# FunctionalSchematic.net
KiCad netlist of a schematic drawn in Altium Designer
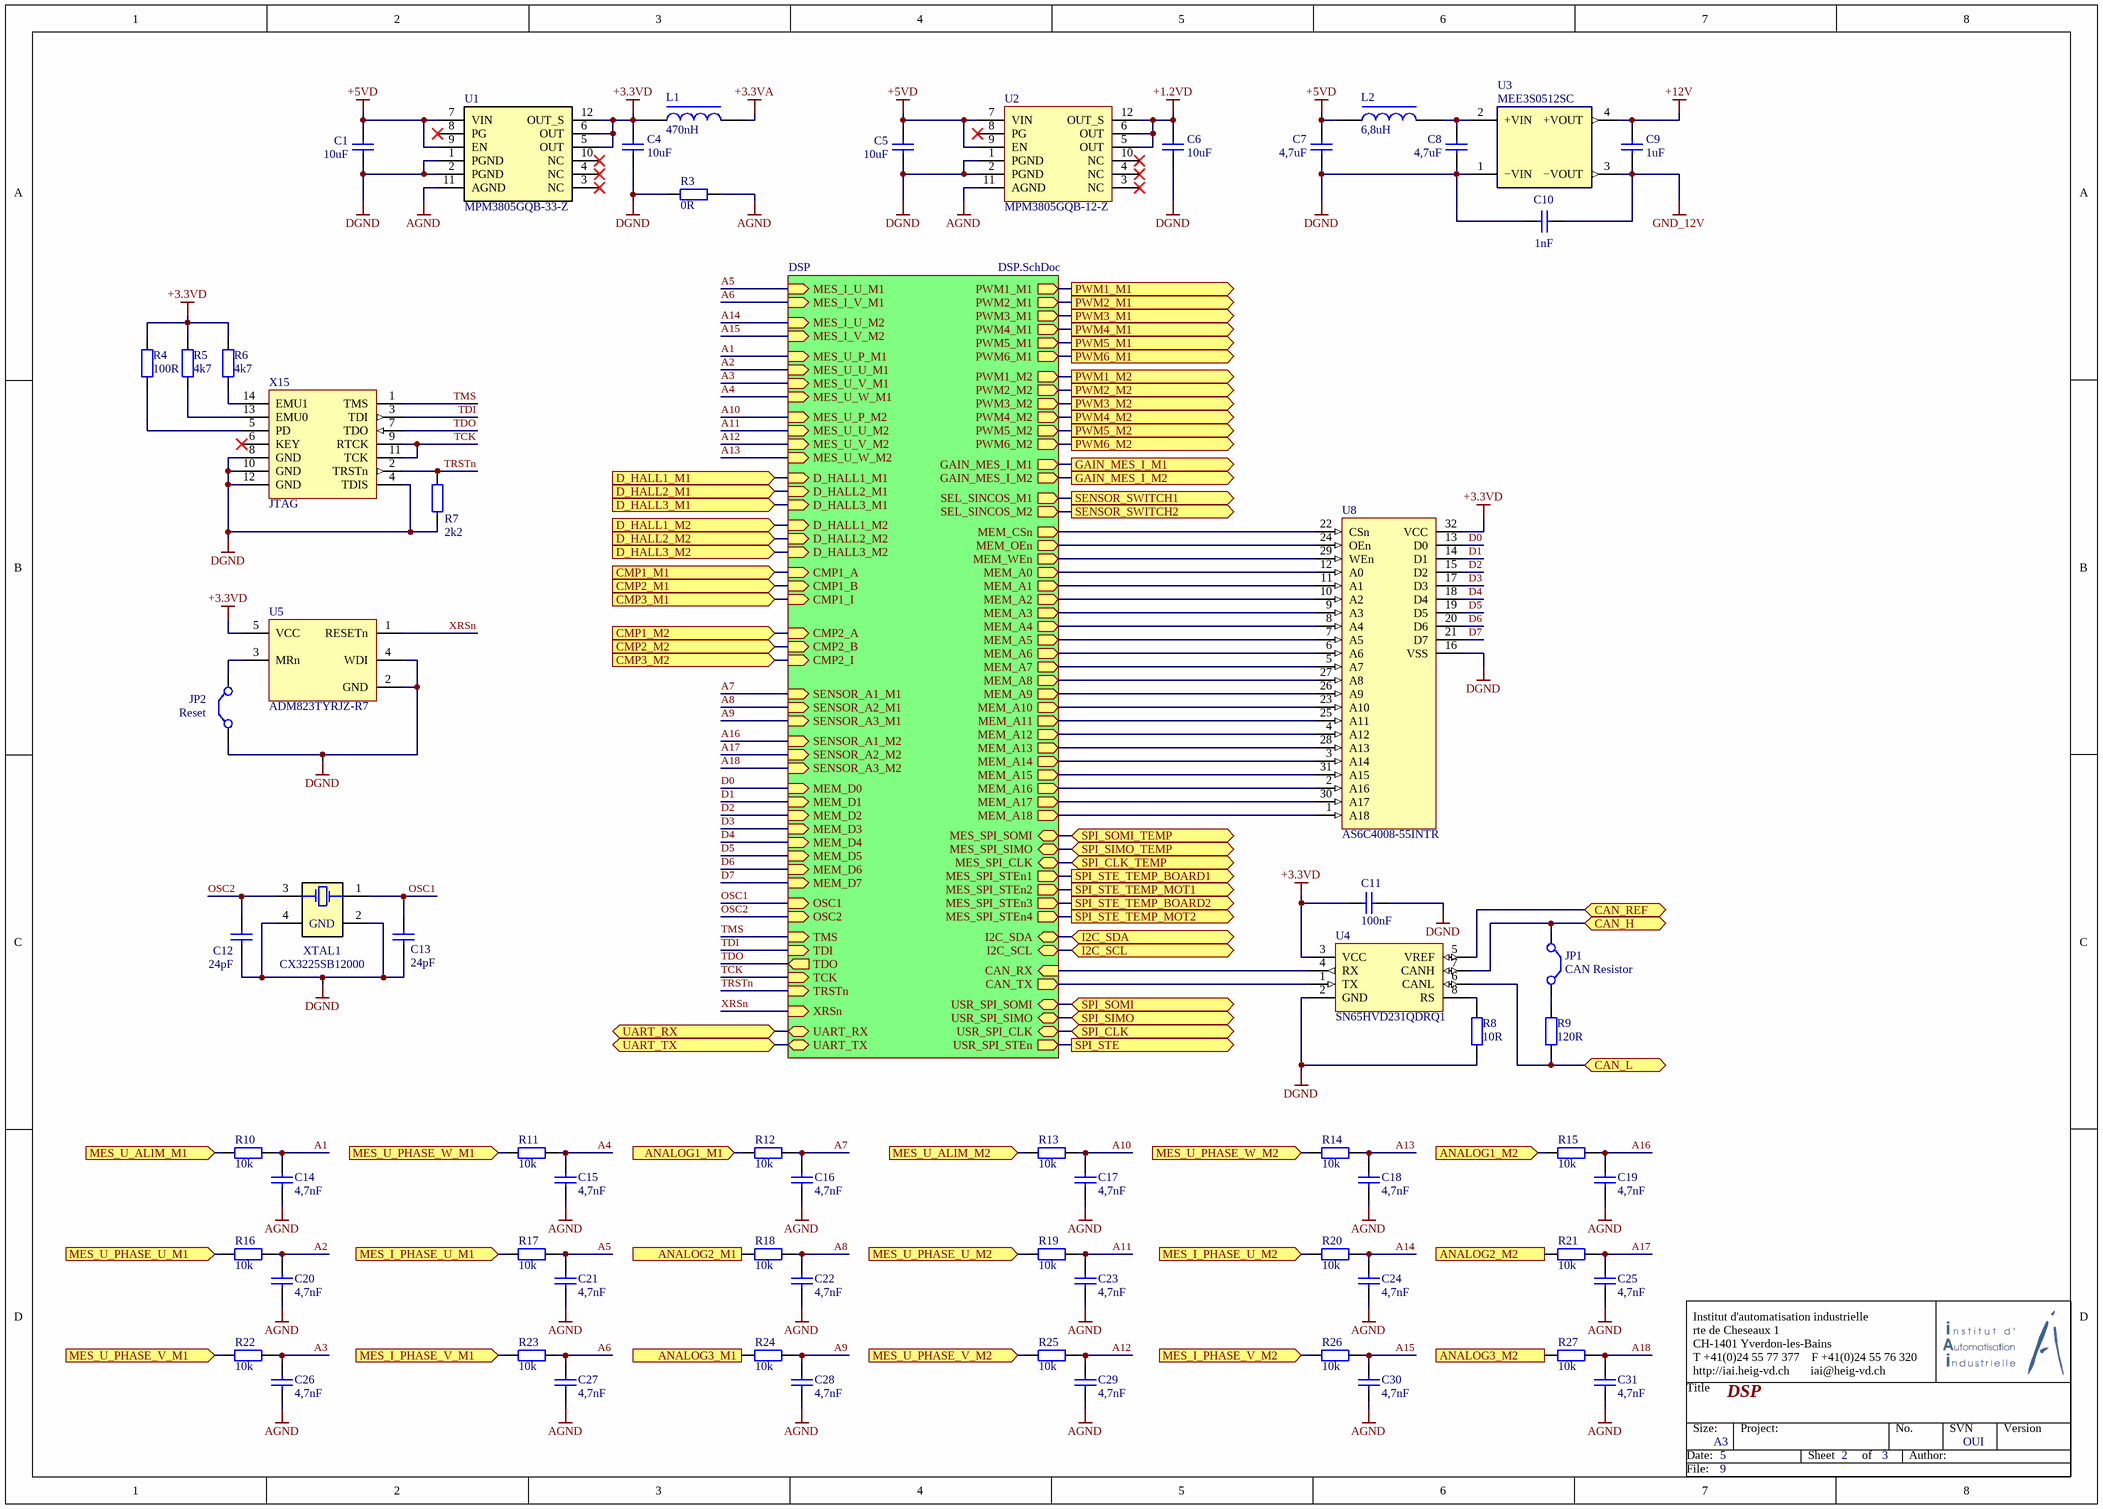
[diagram p0: FunctionalSchematic.SchDoc]

(export (version "E")
  (design (tool "Eeschema 10.0.6"))
  (components
    (comp (ref "C1")
      (value "10uF")
      (footprint "CommandBoard:CAPC1608X08N")
      (description "10µF ±20% 10V Condensateurs céramique X5R 0603 (1608 métrique)")
      (fields (field (name "Comment") "CAP CER 10uF 0603"))
      (libsource (lib "CommandBoard") (part "CAP CER 10uF 10% 10V 0603"))
    )
    (comp (ref "C4")
      (value "10uF")
      (footprint "CommandBoard:CAPC1608X08N")
      (description "10µF ±20% 10V Condensateurs céramique X5R 0603 (1608 métrique)")
      (fields (field (name "Comment") "CAP CER 10uF 0603"))
      (libsource (lib "CommandBoard") (part "CAP CER 10uF 10% 10V 0603"))
    )
    (comp (ref "C5")
      (value "10uF")
      (footprint "CommandBoard:CAPC1608X08N")
      (description "10µF ±20% 10V Condensateurs céramique X5R 0603 (1608 métrique)")
      (fields (field (name "Comment") "CAP CER 10uF 0603"))
      (libsource (lib "CommandBoard") (part "CAP CER 10uF 10% 10V 0603"))
    )
    (comp (ref "C6")
      (value "10uF")
      (footprint "CommandBoard:CAPC1608X08N")
      (description "10µF ±20% 10V Condensateurs céramique X5R 0603 (1608 métrique)")
      (fields (field (name "Comment") "CAP CER 10uF 0603"))
      (libsource (lib "CommandBoard") (part "CAP CER 10uF 10% 10V 0603"))
    )
    (comp (ref "C7")
      (value "4,7uF")
      (footprint "CommandBoard:CAPC1608X08N")
      (description "4,7µF ±20% 10V Condensateurs céramique X5R 0603 (1608 métrique)")
      (fields (field (name "Comment") "CAP CER 4.7uF 0603"))
      (libsource (lib "CommandBoard") (part "CAP CER 4.7uF 10% 10V 0603"))
    )
    (comp (ref "C8")
      (value "4,7uF")
      (footprint "CommandBoard:CAPC1608X08N")
      (description "4,7µF ±20% 10V Condensateurs céramique X5R 0603 (1608 métrique)")
      (fields (field (name "Comment") "CAP CER 4.7uF 0603"))
      (libsource (lib "CommandBoard") (part "CAP CER 4.7uF 10% 10V 0603"))
    )
    (comp (ref "C9")
      (value "1uF")
      (footprint "CommandBoard:CAPC1608X08N")
      (description "1µF ±10% 16V Condensateurs céramique X7R 0603 (1608 métrique)")
      (fields (field (name "Comment") "CAP CER 1uF 0603"))
      (libsource (lib "CommandBoard") (part "CAP CER 1uF 10% 16V 0603"))
    )
    (comp (ref "C10")
      (value "1nF")
      (footprint "CommandBoard:CAPC1608X08N")
      (description "1nF ±10% 10V Condensateurs céramique X7R 0603 (1608 métrique)")
      (fields (field (name "Comment") "CAP CER 1nF 0603"))
      (libsource (lib "CommandBoard") (part "CAP CER 1nF 10% 10V 0603"))
    )
    (comp (ref "C11")
      (value "100nF")
      (footprint "CommandBoard:CAPC1608X08N")
      (description "0,1µF ±10% 10V Condensateurs céramique X7R 0603 (1608 métrique)")
      (fields (field (name "Comment") "CAP CER 100nF 0603"))
      (libsource (lib "CommandBoard") (part "CAP CER 100nF 10% 10V 0603"))
    )
    (comp (ref "C12")
      (value "24pF")
      (footprint "CommandBoard:CAPC1608X08N")
      (description "24pF ±10% 10V Condensateurs céramique X7R 0603 (1608 métrique)")
      (fields (field (name "Comment") "CAP CER 1nF 0603"))
      (libsource (lib "CommandBoard") (part "CAP CER 24pF 10% 10V 0603"))
    )
    (comp (ref "C13")
      (value "24pF")
      (footprint "CommandBoard:CAPC1608X08N")
      (description "24pF ±10% 10V Condensateurs céramique X7R 0603 (1608 métrique)")
      (fields (field (name "Comment") "CAP CER 1nF 0603"))
      (libsource (lib "CommandBoard") (part "CAP CER 24pF 10% 10V 0603"))
    )
    (comp (ref "C14")
      (value "4,7nF")
      (footprint "CommandBoard:CAPC1608X08N")
      (description "4,7nF ±10% 10V Condensateurs céramique X7R 0603 (1608 métrique)")
      (fields (field (name "Comment") "CAP CER 4.7nF 0603"))
      (libsource (lib "CommandBoard") (part "CAP CER 4.7nF 10% 10V 0603"))
    )
    (comp (ref "C15")
      (value "4,7nF")
      (footprint "CommandBoard:CAPC1608X08N")
      (description "4,7nF ±10% 10V Condensateurs céramique X7R 0603 (1608 métrique)")
      (fields (field (name "Comment") "CAP CER 4.7nF 0603"))
      (libsource (lib "CommandBoard") (part "CAP CER 4.7nF 10% 10V 0603"))
    )
    (comp (ref "C16")
      (value "4,7nF")
      (footprint "CommandBoard:CAPC1608X08N")
      (description "4,7nF ±10% 10V Condensateurs céramique X7R 0603 (1608 métrique)")
      (fields (field (name "Comment") "CAP CER 4.7nF 0603"))
      (libsource (lib "CommandBoard") (part "CAP CER 4.7nF 10% 10V 0603"))
    )
    (comp (ref "C17")
      (value "4,7nF")
      (footprint "CommandBoard:CAPC1608X08N")
      (description "4,7nF ±10% 10V Condensateurs céramique X7R 0603 (1608 métrique)")
      (fields (field (name "Comment") "CAP CER 4.7nF 0603"))
      (libsource (lib "CommandBoard") (part "CAP CER 4.7nF 10% 10V 0603"))
    )
    (comp (ref "C18")
      (value "4,7nF")
      (footprint "CommandBoard:CAPC1608X08N")
      (description "4,7nF ±10% 10V Condensateurs céramique X7R 0603 (1608 métrique)")
      (fields (field (name "Comment") "CAP CER 4.7nF 0603"))
      (libsource (lib "CommandBoard") (part "CAP CER 4.7nF 10% 10V 0603"))
    )
    (comp (ref "C19")
      (value "4,7nF")
      (footprint "CommandBoard:CAPC1608X08N")
      (description "4,7nF ±10% 10V Condensateurs céramique X7R 0603 (1608 métrique)")
      (fields (field (name "Comment") "CAP CER 4.7nF 0603"))
      (libsource (lib "CommandBoard") (part "CAP CER 4.7nF 10% 10V 0603"))
    )
    (comp (ref "C20")
      (value "4,7nF")
      (footprint "CommandBoard:CAPC1608X08N")
      (description "4,7nF ±10% 10V Condensateurs céramique X7R 0603 (1608 métrique)")
      (fields (field (name "Comment") "CAP CER 4.7nF 0603"))
      (libsource (lib "CommandBoard") (part "CAP CER 4.7nF 10% 10V 0603"))
    )
    (comp (ref "C21")
      (value "4,7nF")
      (footprint "CommandBoard:CAPC1608X08N")
      (description "4,7nF ±10% 10V Condensateurs céramique X7R 0603 (1608 métrique)")
      (fields (field (name "Comment") "CAP CER 4.7nF 0603"))
      (libsource (lib "CommandBoard") (part "CAP CER 4.7nF 10% 10V 0603"))
    )
    (comp (ref "C22")
      (value "4,7nF")
      (footprint "CommandBoard:CAPC1608X08N")
      (description "4,7nF ±10% 10V Condensateurs céramique X7R 0603 (1608 métrique)")
      (fields (field (name "Comment") "CAP CER 4.7nF 0603"))
      (libsource (lib "CommandBoard") (part "CAP CER 4.7nF 10% 10V 0603"))
    )
    (comp (ref "C23")
      (value "4,7nF")
      (footprint "CommandBoard:CAPC1608X08N")
      (description "4,7nF ±10% 10V Condensateurs céramique X7R 0603 (1608 métrique)")
      (fields (field (name "Comment") "CAP CER 4.7nF 0603"))
      (libsource (lib "CommandBoard") (part "CAP CER 4.7nF 10% 10V 0603"))
    )
    (comp (ref "C24")
      (value "4,7nF")
      (footprint "CommandBoard:CAPC1608X08N")
      (description "4,7nF ±10% 10V Condensateurs céramique X7R 0603 (1608 métrique)")
      (fields (field (name "Comment") "CAP CER 4.7nF 0603"))
      (libsource (lib "CommandBoard") (part "CAP CER 4.7nF 10% 10V 0603"))
    )
    (comp (ref "C25")
      (value "4,7nF")
      (footprint "CommandBoard:CAPC1608X08N")
      (description "4,7nF ±10% 10V Condensateurs céramique X7R 0603 (1608 métrique)")
      (fields (field (name "Comment") "CAP CER 4.7nF 0603"))
      (libsource (lib "CommandBoard") (part "CAP CER 4.7nF 10% 10V 0603"))
    )
    (comp (ref "C26")
      (value "4,7nF")
      (footprint "CommandBoard:CAPC1608X08N")
      (description "4,7nF ±10% 10V Condensateurs céramique X7R 0603 (1608 métrique)")
      (fields (field (name "Comment") "CAP CER 4.7nF 0603"))
      (libsource (lib "CommandBoard") (part "CAP CER 4.7nF 10% 10V 0603"))
    )
    (comp (ref "C27")
      (value "4,7nF")
      (footprint "CommandBoard:CAPC1608X08N")
      (description "4,7nF ±10% 10V Condensateurs céramique X7R 0603 (1608 métrique)")
      (fields (field (name "Comment") "CAP CER 4.7nF 0603"))
      (libsource (lib "CommandBoard") (part "CAP CER 4.7nF 10% 10V 0603"))
    )
    (comp (ref "C28")
      (value "4,7nF")
      (footprint "CommandBoard:CAPC1608X08N")
      (description "4,7nF ±10% 10V Condensateurs céramique X7R 0603 (1608 métrique)")
      (fields (field (name "Comment") "CAP CER 4.7nF 0603"))
      (libsource (lib "CommandBoard") (part "CAP CER 4.7nF 10% 10V 0603"))
    )
    (comp (ref "C29")
      (value "4,7nF")
      (footprint "CommandBoard:CAPC1608X08N")
      (description "4,7nF ±10% 10V Condensateurs céramique X7R 0603 (1608 métrique)")
      (fields (field (name "Comment") "CAP CER 4.7nF 0603"))
      (libsource (lib "CommandBoard") (part "CAP CER 4.7nF 10% 10V 0603"))
    )
    (comp (ref "C30")
      (value "4,7nF")
      (footprint "CommandBoard:CAPC1608X08N")
      (description "4,7nF ±10% 10V Condensateurs céramique X7R 0603 (1608 métrique)")
      (fields (field (name "Comment") "CAP CER 4.7nF 0603"))
      (libsource (lib "CommandBoard") (part "CAP CER 4.7nF 10% 10V 0603"))
    )
    (comp (ref "C31")
      (value "4,7nF")
      (footprint "CommandBoard:CAPC1608X08N")
      (description "4,7nF ±10% 10V Condensateurs céramique X7R 0603 (1608 métrique)")
      (fields (field (name "Comment") "CAP CER 4.7nF 0603"))
      (libsource (lib "CommandBoard") (part "CAP CER 4.7nF 10% 10V 0603"))
    )
    (comp (ref "JP1")
      (value "CONNECT 2pos 90°")
      (footprint "CommandBoard:62000211121")
      (fields (field (name "USE") "CAN Resistor"))
      (libsource (lib "CommandBoard") (part "CONNECT 2pos 90° 3.81mm"))
    )
    (comp (ref "JP2")
      (value "CONNECT 2pos 90°")
      (footprint "CommandBoard:62000211121")
      (fields (field (name "USE") "Reset"))
      (libsource (lib "CommandBoard") (part "CONNECT 2pos 90° 3.81mm"))
    )
    (comp (ref "L1")
      (value "470nH")
      (footprint "CommandBoard:INDC2016X10N")
      (fields (field (name "Comment") "IND SMD 470nH 0806"))
      (libsource (lib "CommandBoard") (part "IND SMD 470nH 0806"))
    )
    (comp (ref "L2")
      (value "6,8uH")
      (footprint "CommandBoard:INDC1608X10N")
      (description "6,8µH Blindé Multicouche Inducteur 15mA 1,3Ohms maxi 0603 (1608 métrique)")
      (fields (field (name "Comment") "IND SMD 0603"))
      (libsource (lib "CommandBoard") (part "IND SMD 6.8uH 0603"))
    )
    (comp (ref "R3")
      (value "0R")
      (footprint "CommandBoard:RESC1508X04N")
      (description "Resistance 0 OHM")
      (fields (field (name "Comment") "RES SMD 0R 0603"))
      (libsource (lib "CommandBoard") (part "RES SMD 0 OHM 1% 1/10W 0603"))
    )
    (comp (ref "R4")
      (value "100R")
      (footprint "CommandBoard:RESC1508X04N")
      (description "100 Ohms ±1% 0,1W, 1/10W Pavé résistif 0603 (1608 métrique) AutomobileAEC-Q200 Couche épaisse")
      (fields (field (name "Comment") "RES SMD 100R 0603"))
      (libsource (lib "CommandBoard") (part "RES SMD 100 OHM 1% 1/10W 0603"))
    )
    (comp (ref "R5")
      (value "4k7")
      (footprint "CommandBoard:RESC1508X04N")
      (description "4,7 kOhms ±1% 0,1W, 1/10W Pavé résistif 0603 (1608 métrique) AutomobileAEC-Q200 Couche épaisse")
      (fields (field (name "Comment") "RES SMD 4.7k 0603"))
      (libsource (lib "CommandBoard") (part "RES SMD 4.7k OHM 1% 1/10W 0603"))
    )
    (comp (ref "R6")
      (value "4k7")
      (footprint "CommandBoard:RESC1508X04N")
      (description "4,7 kOhms ±1% 0,1W, 1/10W Pavé résistif 0603 (1608 métrique) AutomobileAEC-Q200 Couche épaisse")
      (fields (field (name "Comment") "RES SMD 4.7k 0603"))
      (libsource (lib "CommandBoard") (part "RES SMD 4.7k OHM 1% 1/10W 0603"))
    )
    (comp (ref "R7")
      (value "2k2")
      (footprint "CommandBoard:RESC1508X04N")
      (description "2,2 kOhms ±1% 0,1W, 1/10W Pavé résistif 0603 (1608 métrique) AutomobileAEC-Q200 Couche épaisse")
      (fields (field (name "Comment") "RES SMD 2K2 0603"))
      (libsource (lib "CommandBoard") (part "RES SMD 2K2 OHM 1% 1/10W 0603"))
    )
    (comp (ref "R8")
      (value "10R")
      (footprint "CommandBoard:RESC1508X04N")
      (description "10 Ohms ±1% 0,1W, 1/10W Pavé résistif 0603 (1608 métrique) AutomobileAEC-Q200 Couche épaisse")
      (fields (field (name "Comment") "RES SMD 10R 0603"))
      (libsource (lib "CommandBoard") (part "RES SMD 10 OHM 1% 1/10W 0603"))
    )
    (comp (ref "R9")
      (value "120R")
      (footprint "CommandBoard:RESC1508X04N")
      (description "120 Ohms ±1% 0,1W, 1/10W Pavé résistif 0603 (1608 métrique) AutomobileAEC-Q200 Couche épaisse")
      (fields (field (name "Comment") "RES SMD 120R 0603"))
      (libsource (lib "CommandBoard") (part "RES SMD 120 OHM 1% 1/10W 0603"))
    )
    (comp (ref "R10")
      (value "10k")
      (footprint "CommandBoard:RESC1508X04N")
      (description "10 kOhms ±1% 0,1W, 1/10W Pavé résistif 0603 (1608 métrique) AutomobileAEC-Q200 Couche épaisse")
      (fields (field (name "Comment") "RES 10K SMD 0603"))
      (libsource (lib "CommandBoard") (part "RES SMD 10K OHM 1% 1/10W 0603"))
    )
    (comp (ref "R11")
      (value "10k")
      (footprint "CommandBoard:RESC1508X04N")
      (description "10 kOhms ±1% 0,1W, 1/10W Pavé résistif 0603 (1608 métrique) AutomobileAEC-Q200 Couche épaisse")
      (fields (field (name "Comment") "RES 10K SMD 0603"))
      (libsource (lib "CommandBoard") (part "RES SMD 10K OHM 1% 1/10W 0603"))
    )
    (comp (ref "R12")
      (value "10k")
      (footprint "CommandBoard:RESC1508X04N")
      (description "10 kOhms ±1% 0,1W, 1/10W Pavé résistif 0603 (1608 métrique) AutomobileAEC-Q200 Couche épaisse")
      (fields (field (name "Comment") "RES 10K SMD 0603"))
      (libsource (lib "CommandBoard") (part "RES SMD 10K OHM 1% 1/10W 0603"))
    )
    (comp (ref "R13")
      (value "10k")
      (footprint "CommandBoard:RESC1508X04N")
      (description "10 kOhms ±1% 0,1W, 1/10W Pavé résistif 0603 (1608 métrique) AutomobileAEC-Q200 Couche épaisse")
      (fields (field (name "Comment") "RES 10K SMD 0603"))
      (libsource (lib "CommandBoard") (part "RES SMD 10K OHM 1% 1/10W 0603"))
    )
    (comp (ref "R14")
      (value "10k")
      (footprint "CommandBoard:RESC1508X04N")
      (description "10 kOhms ±1% 0,1W, 1/10W Pavé résistif 0603 (1608 métrique) AutomobileAEC-Q200 Couche épaisse")
      (fields (field (name "Comment") "RES 10K SMD 0603"))
      (libsource (lib "CommandBoard") (part "RES SMD 10K OHM 1% 1/10W 0603"))
    )
    (comp (ref "R15")
      (value "10k")
      (footprint "CommandBoard:RESC1508X04N")
      (description "10 kOhms ±1% 0,1W, 1/10W Pavé résistif 0603 (1608 métrique) AutomobileAEC-Q200 Couche épaisse")
      (fields (field (name "Comment") "RES 10K SMD 0603"))
      (libsource (lib "CommandBoard") (part "RES SMD 10K OHM 1% 1/10W 0603"))
    )
    (comp (ref "R16")
      (value "10k")
      (footprint "CommandBoard:RESC1508X04N")
      (description "10 kOhms ±1% 0,1W, 1/10W Pavé résistif 0603 (1608 métrique) AutomobileAEC-Q200 Couche épaisse")
      (fields (field (name "Comment") "RES 10K SMD 0603"))
      (libsource (lib "CommandBoard") (part "RES SMD 10K OHM 1% 1/10W 0603"))
    )
    (comp (ref "R17")
      (value "10k")
      (footprint "CommandBoard:RESC1508X04N")
      (description "10 kOhms ±1% 0,1W, 1/10W Pavé résistif 0603 (1608 métrique) AutomobileAEC-Q200 Couche épaisse")
      (fields (field (name "Comment") "RES 10K SMD 0603"))
      (libsource (lib "CommandBoard") (part "RES SMD 10K OHM 1% 1/10W 0603"))
    )
    (comp (ref "R18")
      (value "10k")
      (footprint "CommandBoard:RESC1508X04N")
      (description "10 kOhms ±1% 0,1W, 1/10W Pavé résistif 0603 (1608 métrique) AutomobileAEC-Q200 Couche épaisse")
      (fields (field (name "Comment") "RES 10K SMD 0603"))
      (libsource (lib "CommandBoard") (part "RES SMD 10K OHM 1% 1/10W 0603"))
    )
    (comp (ref "R19")
      (value "10k")
      (footprint "CommandBoard:RESC1508X04N")
      (description "10 kOhms ±1% 0,1W, 1/10W Pavé résistif 0603 (1608 métrique) AutomobileAEC-Q200 Couche épaisse")
      (fields (field (name "Comment") "RES 10K SMD 0603"))
      (libsource (lib "CommandBoard") (part "RES SMD 10K OHM 1% 1/10W 0603"))
    )
    (comp (ref "R20")
      (value "10k")
      (footprint "CommandBoard:RESC1508X04N")
      (description "10 kOhms ±1% 0,1W, 1/10W Pavé résistif 0603 (1608 métrique) AutomobileAEC-Q200 Couche épaisse")
      (fields (field (name "Comment") "RES 10K SMD 0603"))
      (libsource (lib "CommandBoard") (part "RES SMD 10K OHM 1% 1/10W 0603"))
    )
    (comp (ref "R21")
      (value "10k")
      (footprint "CommandBoard:RESC1508X04N")
      (description "10 kOhms ±1% 0,1W, 1/10W Pavé résistif 0603 (1608 métrique) AutomobileAEC-Q200 Couche épaisse")
      (fields (field (name "Comment") "RES 10K SMD 0603"))
      (libsource (lib "CommandBoard") (part "RES SMD 10K OHM 1% 1/10W 0603"))
    )
    (comp (ref "R22")
      (value "10k")
      (footprint "CommandBoard:RESC1508X04N")
      (description "10 kOhms ±1% 0,1W, 1/10W Pavé résistif 0603 (1608 métrique) AutomobileAEC-Q200 Couche épaisse")
      (fields (field (name "Comment") "RES 10K SMD 0603"))
      (libsource (lib "CommandBoard") (part "RES SMD 10K OHM 1% 1/10W 0603"))
    )
    (comp (ref "R23")
      (value "10k")
      (footprint "CommandBoard:RESC1508X04N")
      (description "10 kOhms ±1% 0,1W, 1/10W Pavé résistif 0603 (1608 métrique) AutomobileAEC-Q200 Couche épaisse")
      (fields (field (name "Comment") "RES 10K SMD 0603"))
      (libsource (lib "CommandBoard") (part "RES SMD 10K OHM 1% 1/10W 0603"))
    )
    (comp (ref "R24")
      (value "10k")
      (footprint "CommandBoard:RESC1508X04N")
      (description "10 kOhms ±1% 0,1W, 1/10W Pavé résistif 0603 (1608 métrique) AutomobileAEC-Q200 Couche épaisse")
      (fields (field (name "Comment") "RES 10K SMD 0603"))
      (libsource (lib "CommandBoard") (part "RES SMD 10K OHM 1% 1/10W 0603"))
    )
    (comp (ref "R25")
      (value "10k")
      (footprint "CommandBoard:RESC1508X04N")
      (description "10 kOhms ±1% 0,1W, 1/10W Pavé résistif 0603 (1608 métrique) AutomobileAEC-Q200 Couche épaisse")
      (fields (field (name "Comment") "RES 10K SMD 0603"))
      (libsource (lib "CommandBoard") (part "RES SMD 10K OHM 1% 1/10W 0603"))
    )
    (comp (ref "R26")
      (value "10k")
      (footprint "CommandBoard:RESC1508X04N")
      (description "10 kOhms ±1% 0,1W, 1/10W Pavé résistif 0603 (1608 métrique) AutomobileAEC-Q200 Couche épaisse")
      (fields (field (name "Comment") "RES 10K SMD 0603"))
      (libsource (lib "CommandBoard") (part "RES SMD 10K OHM 1% 1/10W 0603"))
    )
    (comp (ref "R27")
      (value "10k")
      (footprint "CommandBoard:RESC1508X04N")
      (description "10 kOhms ±1% 0,1W, 1/10W Pavé résistif 0603 (1608 métrique) AutomobileAEC-Q200 Couche épaisse")
      (fields (field (name "Comment") "RES 10K SMD 0603"))
      (libsource (lib "CommandBoard") (part "RES SMD 10K OHM 1% 1/10W 0603"))
    )
    (comp (ref "U1")
      (value "MPM3805GQB-33-Z")
      (footprint "CommandBoard:QFN2p5x3p0x0p9_MNP")
      (description "Module PoL non isolé Convertisseurs CC/CC 1 Sortie 3,3V 600mA 2,5V - 6V Entrée")
      (fields (field (name "Comment") "DC DC CONVERTER 5V-3.3V"))
      (libsource (lib "CommandBoard") (part "DC DC CONVERTER 5V-3.3V 2W"))
    )
    (comp (ref "U2")
      (value "MPM3805GQB-12-Z")
      (footprint "CommandBoard:QFN2p5x3p0x0p9_MNP")
      (description "Module PoL non isolé Convertisseurs CC/CC 1 Sortie 1,2V 600mA 2,5V - 6V Entrée")
      (fields (field (name "Comment") "DC DC CONVERTER 5V-1.2V"))
      (libsource (lib "CommandBoard") (part "DC DC CONVERTER 5V-1.2V 720mW"))
    )
    (comp (ref "U3")
      (value "MEE3S0512SC")
      (footprint "CommandBoard:DCDC CONVERTER")
      (description "Module isolé Convertisseurs CC/CC 1 Sortie 12V 250mA 4,5V - 5,5V Entrée")
      (fields (field (name "Comment") "DC DC CONVERTER 5V-12V"))
      (libsource (lib "CommandBoard") (part "DC DC CONVERTER 5V-12V 3W"))
    )
    (comp (ref "U4")
      (value "SN65HVD231QDRQ1")
      (footprint "CommandBoard:SOIC127P600X175-8N")
      (description "Émetteur-récepteur 1/1 Semi CANbus 8-SOIC")
      (fields (field (name "Comment") "IC TRANSCEIVER CAN"))
      (libsource (lib "CommandBoard") (part "IC TRANSCEIVER HALF 1/1 8SOIC"))
    )
    (comp (ref "U5")
      (value "ADM823TYRJZ-R7")
      (footprint "CommandBoard:SOT95P280X145-5N")
      (description "Superviseur Pousser-tirer/Totem pôle 1 canal SOT-23-5")
      (fields (field (name "Comment") "SUPERVISOR 1 CHANNEL"))
      (libsource (lib "CommandBoard") (part "IC SUPERVISOR 1 CHANNEL SOT23-5"))
    )
    (comp (ref "U8")
      (value "AS6C4008-55INTR")
      (footprint "CommandBoard:SOP127P1410X300-32N")
      (description "IC RAM 8MBIT SPI 10MHZ 8SOP")
      (fields (field (name "Comment") "RAM SPI"))
      (libsource (lib "CommandBoard") (part "RAM"))
    )
    (comp (ref "X15")
      (value "CONNECT SMD 7x2pos 180°")
      (footprint "CommandBoard:62101421021")
      (fields (field (name "USE") "JTAG"))
      (libsource (lib "CommandBoard") (part "CONNECT SMD 7x2pos 180° 2.54mm"))
    )
    (comp (ref "XTAL1")
      (value "CX3225SB12000")
      (footprint "CommandBoard:OSCCC320X250X60N")
      (description "CRYSTAL 12.0000MHZ 8PF SMD")
      (fields (field (name "Comment") "CRYSTAL 12.0000MHZ"))
      (libsource (lib "CommandBoard") (part "OSCILLATOR 12MHz"))
    )
  )
  (nets
    (net (code "1") (name "+1.2VD") (class "Default")
      (node (ref "C6") (pin "2") (pinfunction "2_2") (pintype "passive"))
      (node (ref "U2") (pin "12") (pinfunction "OUT_S_12") (pintype "power_in"))
      (node (ref "U2") (pin "5") (pinfunction "OUT_5") (pintype "power_in"))
      (node (ref "U2") (pin "6") (pinfunction "OUT_6") (pintype "power_in"))
    )
    (net (code "2") (name "+3.3VA") (class "Default")
      (node (ref "L1") (pin "2") (pinfunction "2_2") (pintype "passive"))
    )
    (net (code "3") (name "+3.3VD") (class "Default")
      (node (ref "C11") (pin "1") (pinfunction "1_1") (pintype "passive"))
      (node (ref "C4") (pin "2") (pinfunction "2_2") (pintype "passive"))
      (node (ref "L1") (pin "1") (pinfunction "1_1") (pintype "passive"))
      (node (ref "R4") (pin "2") (pinfunction "2_2") (pintype "passive"))
      (node (ref "R5") (pin "2") (pinfunction "2_2") (pintype "passive"))
      (node (ref "R6") (pin "2") (pinfunction "2_2") (pintype "passive"))
      (node (ref "U1") (pin "12") (pinfunction "OUT_S_12") (pintype "power_in"))
      (node (ref "U1") (pin "5") (pinfunction "OUT_5") (pintype "power_in"))
      (node (ref "U1") (pin "6") (pinfunction "OUT_6") (pintype "power_in"))
      (node (ref "U4") (pin "3") (pinfunction "VCC_3") (pintype "power_in"))
      (node (ref "U5") (pin "5") (pinfunction "VCC_5") (pintype "power_in"))
      (node (ref "U8") (pin "32") (pinfunction "VCC_32") (pintype "power_in"))
    )
    (net (code "4") (name "+5VD") (class "Default")
      (node (ref "C1") (pin "2") (pinfunction "2_2") (pintype "passive"))
      (node (ref "C5") (pin "2") (pinfunction "2_2") (pintype "passive"))
      (node (ref "C7") (pin "2") (pinfunction "2_2") (pintype "passive"))
      (node (ref "L2") (pin "1") (pinfunction "1_1") (pintype "passive"))
      (node (ref "U1") (pin "7") (pinfunction "VIN_7") (pintype "power_in"))
      (node (ref "U1") (pin "9") (pinfunction "EN_9") (pintype "power_in"))
      (node (ref "U2") (pin "7") (pinfunction "VIN_7") (pintype "power_in"))
      (node (ref "U2") (pin "9") (pinfunction "EN_9") (pintype "power_in"))
    )
    (net (code "5") (name "+12V") (class "Default")
      (node (ref "C9") (pin "2") (pinfunction "2_2") (pintype "passive"))
      (node (ref "U3") (pin "4") (pinfunction "+VOUT_4") (pintype "output"))
    )
    (net (code "6") (name "/A1") (class "Default")
      (node (ref "C14") (pin "2") (pinfunction "2_2") (pintype "passive"))
      (node (ref "R10") (pin "2") (pinfunction "2_2") (pintype "passive"))
    )
    (net (code "7") (name "/A2") (class "Default")
      (node (ref "C20") (pin "2") (pinfunction "2_2") (pintype "passive"))
      (node (ref "R16") (pin "2") (pinfunction "2_2") (pintype "passive"))
    )
    (net (code "8") (name "/A3") (class "Default")
      (node (ref "C26") (pin "2") (pinfunction "2_2") (pintype "passive"))
      (node (ref "R22") (pin "2") (pinfunction "2_2") (pintype "passive"))
    )
    (net (code "9") (name "/A4") (class "Default")
      (node (ref "C15") (pin "2") (pinfunction "2_2") (pintype "passive"))
      (node (ref "R11") (pin "2") (pinfunction "2_2") (pintype "passive"))
    )
    (net (code "10") (name "/A5") (class "Default")
      (node (ref "C21") (pin "2") (pinfunction "2_2") (pintype "passive"))
      (node (ref "R17") (pin "2") (pinfunction "2_2") (pintype "passive"))
    )
    (net (code "11") (name "/A6") (class "Default")
      (node (ref "C27") (pin "2") (pinfunction "2_2") (pintype "passive"))
      (node (ref "R23") (pin "2") (pinfunction "2_2") (pintype "passive"))
    )
    (net (code "12") (name "/A7") (class "Default")
      (node (ref "C16") (pin "2") (pinfunction "2_2") (pintype "passive"))
      (node (ref "R12") (pin "2") (pinfunction "2_2") (pintype "passive"))
    )
    (net (code "13") (name "/A8") (class "Default")
      (node (ref "C22") (pin "2") (pinfunction "2_2") (pintype "passive"))
      (node (ref "R18") (pin "2") (pinfunction "2_2") (pintype "passive"))
    )
    (net (code "14") (name "/A9") (class "Default")
      (node (ref "C28") (pin "2") (pinfunction "2_2") (pintype "passive"))
      (node (ref "R24") (pin "2") (pinfunction "2_2") (pintype "passive"))
    )
    (net (code "15") (name "/A10") (class "Default")
      (node (ref "C17") (pin "2") (pinfunction "2_2") (pintype "passive"))
      (node (ref "R13") (pin "2") (pinfunction "2_2") (pintype "passive"))
    )
    (net (code "16") (name "/A11") (class "Default")
      (node (ref "C23") (pin "2") (pinfunction "2_2") (pintype "passive"))
      (node (ref "R19") (pin "2") (pinfunction "2_2") (pintype "passive"))
    )
    (net (code "17") (name "/A12") (class "Default")
      (node (ref "C29") (pin "2") (pinfunction "2_2") (pintype "passive"))
      (node (ref "R25") (pin "2") (pinfunction "2_2") (pintype "passive"))
    )
    (net (code "18") (name "/A13") (class "Default")
      (node (ref "C18") (pin "2") (pinfunction "2_2") (pintype "passive"))
      (node (ref "R14") (pin "2") (pinfunction "2_2") (pintype "passive"))
    )
    (net (code "19") (name "/A14") (class "Default")
      (node (ref "C24") (pin "2") (pinfunction "2_2") (pintype "passive"))
      (node (ref "R20") (pin "2") (pinfunction "2_2") (pintype "passive"))
    )
    (net (code "20") (name "/A15") (class "Default")
      (node (ref "C30") (pin "2") (pinfunction "2_2") (pintype "passive"))
      (node (ref "R26") (pin "2") (pinfunction "2_2") (pintype "passive"))
    )
    (net (code "21") (name "/A16") (class "Default")
      (node (ref "C19") (pin "2") (pinfunction "2_2") (pintype "passive"))
      (node (ref "R15") (pin "2") (pinfunction "2_2") (pintype "passive"))
    )
    (net (code "22") (name "/A17") (class "Default")
      (node (ref "C25") (pin "2") (pinfunction "2_2") (pintype "passive"))
      (node (ref "R21") (pin "2") (pinfunction "2_2") (pintype "passive"))
    )
    (net (code "23") (name "/A18") (class "Default")
      (node (ref "C31") (pin "2") (pinfunction "2_2") (pintype "passive"))
      (node (ref "R27") (pin "2") (pinfunction "2_2") (pintype "passive"))
    )
    (net (code "24") (name "/ANALOG1_M1") (class "Default")
      (node (ref "R12") (pin "1") (pinfunction "1_1") (pintype "passive"))
    )
    (net (code "25") (name "/ANALOG1_M2") (class "Default")
      (node (ref "R15") (pin "1") (pinfunction "1_1") (pintype "passive"))
    )
    (net (code "26") (name "/ANALOG2_M1") (class "Default")
      (node (ref "R18") (pin "1") (pinfunction "1_1") (pintype "passive"))
    )
    (net (code "27") (name "/ANALOG2_M2") (class "Default")
      (node (ref "R21") (pin "1") (pinfunction "1_1") (pintype "passive"))
    )
    (net (code "28") (name "/ANALOG3_M1") (class "Default")
      (node (ref "R24") (pin "1") (pinfunction "1_1") (pintype "passive"))
    )
    (net (code "29") (name "/ANALOG3_M2") (class "Default")
      (node (ref "R27") (pin "1") (pinfunction "1_1") (pintype "passive"))
    )
    (net (code "30") (name "/CAN_H") (class "Default")
      (node (ref "JP1") (pin "1") (pinfunction "C1_1") (pintype "passive"))
      (node (ref "U4") (pin "7") (pinfunction "CANH_7") (pintype "bidirectional"))
    )
    (net (code "31") (name "/CAN_L") (class "Default")
      (node (ref "R9") (pin "1") (pinfunction "1_1") (pintype "passive"))
      (node (ref "U4") (pin "6") (pinfunction "CANL_6") (pintype "bidirectional"))
    )
    (net (code "32") (name "/CAN_REF") (class "Default")
      (node (ref "U4") (pin "5") (pinfunction "VREF_5") (pintype "bidirectional"))
    )
    (net (code "33") (name "/CAN_RX") (class "Default")
      (node (ref "U4") (pin "4") (pinfunction "RX_4") (pintype "output"))
    )
    (net (code "34") (name "/CAN_TX") (class "Default")
      (node (ref "U4") (pin "1") (pinfunction "TX_1") (pintype "input"))
    )
    (net (code "41") (name "/D0") (class "Default")
      (node (ref "U8") (pin "13") (pinfunction "D0_13") (pintype "power_in"))
    )
    (net (code "42") (name "/D1") (class "Default")
      (node (ref "U8") (pin "14") (pinfunction "D1_14") (pintype "power_in"))
    )
    (net (code "43") (name "/D2") (class "Default")
      (node (ref "U8") (pin "15") (pinfunction "D2_15") (pintype "power_in"))
    )
    (net (code "44") (name "/D3") (class "Default")
      (node (ref "U8") (pin "17") (pinfunction "D3_17") (pintype "power_in"))
    )
    (net (code "45") (name "/D4") (class "Default")
      (node (ref "U8") (pin "18") (pinfunction "D4_18") (pintype "power_in"))
    )
    (net (code "46") (name "/D5") (class "Default")
      (node (ref "U8") (pin "19") (pinfunction "D5_19") (pintype "power_in"))
    )
    (net (code "47") (name "/D6") (class "Default")
      (node (ref "U8") (pin "20") (pinfunction "D6_20") (pintype "power_in"))
    )
    (net (code "48") (name "/D7") (class "Default")
      (node (ref "U8") (pin "21") (pinfunction "D7_21") (pintype "power_in"))
    )
    (net (code "59") (name "/MEM_A0") (class "Default")
      (node (ref "U8") (pin "12") (pinfunction "A0_12") (pintype "input"))
    )
    (net (code "60") (name "/MEM_A1") (class "Default")
      (node (ref "U8") (pin "11") (pinfunction "A1_11") (pintype "input"))
    )
    (net (code "61") (name "/MEM_A2") (class "Default")
      (node (ref "U8") (pin "10") (pinfunction "A2_10") (pintype "input"))
    )
    (net (code "62") (name "/MEM_A3") (class "Default")
      (node (ref "U8") (pin "9") (pinfunction "A3_9") (pintype "input"))
    )
    (net (code "63") (name "/MEM_A4") (class "Default")
      (node (ref "U8") (pin "8") (pinfunction "A4_8") (pintype "input"))
    )
    (net (code "64") (name "/MEM_A5") (class "Default")
      (node (ref "U8") (pin "7") (pinfunction "A5_7") (pintype "input"))
    )
    (net (code "65") (name "/MEM_A6") (class "Default")
      (node (ref "U8") (pin "6") (pinfunction "A6_6") (pintype "input"))
    )
    (net (code "66") (name "/MEM_A7") (class "Default")
      (node (ref "U8") (pin "5") (pinfunction "A7_5") (pintype "input"))
    )
    (net (code "67") (name "/MEM_A8") (class "Default")
      (node (ref "U8") (pin "27") (pinfunction "A8_27") (pintype "input"))
    )
    (net (code "68") (name "/MEM_A9") (class "Default")
      (node (ref "U8") (pin "26") (pinfunction "A9_26") (pintype "input"))
    )
    (net (code "69") (name "/MEM_A10") (class "Default")
      (node (ref "U8") (pin "23") (pinfunction "A10_23") (pintype "input"))
    )
    (net (code "70") (name "/MEM_A11") (class "Default")
      (node (ref "U8") (pin "25") (pinfunction "A11_25") (pintype "input"))
    )
    (net (code "71") (name "/MEM_A12") (class "Default")
      (node (ref "U8") (pin "4") (pinfunction "A12_4") (pintype "input"))
    )
    (net (code "72") (name "/MEM_A13") (class "Default")
      (node (ref "U8") (pin "28") (pinfunction "A13_28") (pintype "input"))
    )
    (net (code "73") (name "/MEM_A14") (class "Default")
      (node (ref "U8") (pin "3") (pinfunction "A14_3") (pintype "input"))
    )
    (net (code "74") (name "/MEM_A15") (class "Default")
      (node (ref "U8") (pin "31") (pinfunction "A15_31") (pintype "input"))
    )
    (net (code "75") (name "/MEM_A16") (class "Default")
      (node (ref "U8") (pin "2") (pinfunction "A16_2") (pintype "input"))
    )
    (net (code "76") (name "/MEM_A17") (class "Default")
      (node (ref "U8") (pin "30") (pinfunction "A17_30") (pintype "input"))
    )
    (net (code "77") (name "/MEM_A18") (class "Default")
      (node (ref "U8") (pin "1") (pinfunction "A18_1") (pintype "input"))
    )
    (net (code "78") (name "/MEM_CSn") (class "Default")
      (node (ref "U8") (pin "22") (pinfunction "CSn_22") (pintype "input"))
    )
    (net (code "79") (name "/MEM_OEn") (class "Default")
      (node (ref "U8") (pin "24") (pinfunction "OEn_24") (pintype "input"))
    )
    (net (code "80") (name "/MEM_WEn") (class "Default")
      (node (ref "U8") (pin "29") (pinfunction "WEn_29") (pintype "input"))
    )
    (net (code "81") (name "/MES_I_PHASE_U_M1") (class "Default")
      (node (ref "R17") (pin "1") (pinfunction "1_1") (pintype "passive"))
    )
    (net (code "82") (name "/MES_I_PHASE_U_M2") (class "Default")
      (node (ref "R20") (pin "1") (pinfunction "1_1") (pintype "passive"))
    )
    (net (code "83") (name "/MES_I_PHASE_V_M1") (class "Default")
      (node (ref "R23") (pin "1") (pinfunction "1_1") (pintype "passive"))
    )
    (net (code "84") (name "/MES_I_PHASE_V_M2") (class "Default")
      (node (ref "R26") (pin "1") (pinfunction "1_1") (pintype "passive"))
    )
    (net (code "85") (name "/MES_U_ALIM_M1") (class "Default")
      (node (ref "R10") (pin "1") (pinfunction "1_1") (pintype "passive"))
    )
    (net (code "86") (name "/MES_U_ALIM_M2") (class "Default")
      (node (ref "R13") (pin "1") (pinfunction "1_1") (pintype "passive"))
    )
    (net (code "87") (name "/MES_U_PHASE_U_M1") (class "Default")
      (node (ref "R16") (pin "1") (pinfunction "1_1") (pintype "passive"))
    )
    (net (code "88") (name "/MES_U_PHASE_U_M2") (class "Default")
      (node (ref "R19") (pin "1") (pinfunction "1_1") (pintype "passive"))
    )
    (net (code "89") (name "/MES_U_PHASE_V_M1") (class "Default")
      (node (ref "R22") (pin "1") (pinfunction "1_1") (pintype "passive"))
    )
    (net (code "90") (name "/MES_U_PHASE_V_M2") (class "Default")
      (node (ref "R25") (pin "1") (pinfunction "1_1") (pintype "passive"))
    )
    (net (code "91") (name "/MES_U_PHASE_W_M1") (class "Default")
      (node (ref "R11") (pin "1") (pinfunction "1_1") (pintype "passive"))
    )
    (net (code "92") (name "/MES_U_PHASE_W_M2") (class "Default")
      (node (ref "R14") (pin "1") (pinfunction "1_1") (pintype "passive"))
    )
    (net (code "93") (name "/OSC1") (class "Default")
      (node (ref "C13") (pin "1") (pinfunction "1_1") (pintype "passive"))
      (node (ref "XTAL1") (pin "1") (pinfunction "OSC1_1") (pintype "passive"))
    )
    (net (code "94") (name "/OSC2") (class "Default")
      (node (ref "C12") (pin "2") (pinfunction "2_2") (pintype "passive"))
      (node (ref "XTAL1") (pin "3") (pinfunction "OSC2_3") (pintype "passive"))
    )
    (net (code "120") (name "/TCK") (class "Default")
      (node (ref "X15") (pin "11") (pinfunction "TCK_11") (pintype "passive"))
      (node (ref "X15") (pin "9") (pinfunction "RTCK_9") (pintype "passive"))
    )
    (net (code "121") (name "/TDI") (class "Default")
      (node (ref "X15") (pin "3") (pinfunction "TDI_3") (pintype "output"))
    )
    (net (code "122") (name "/TDO") (class "Default")
      (node (ref "X15") (pin "7") (pinfunction "TDO_7") (pintype "input"))
    )
    (net (code "123") (name "/TMS") (class "Default")
      (node (ref "X15") (pin "1") (pinfunction "TMS_1") (pintype "passive"))
    )
    (net (code "124") (name "/TRSTn") (class "Default")
      (node (ref "R7") (pin "2") (pinfunction "2_2") (pintype "passive"))
      (node (ref "X15") (pin "2") (pinfunction "TRSTn_2") (pintype "output"))
    )
    (net (code "127") (name "/XRSn") (class "Default")
      (node (ref "U5") (pin "1") (pinfunction "RESETn_1") (pintype "power_in"))
    )
    (net (code "128") (name "AGND") (class "Default")
      (node (ref "C14") (pin "1") (pinfunction "1_1") (pintype "passive"))
      (node (ref "C15") (pin "1") (pinfunction "1_1") (pintype "passive"))
      (node (ref "C16") (pin "1") (pinfunction "1_1") (pintype "passive"))
      (node (ref "C17") (pin "1") (pinfunction "1_1") (pintype "passive"))
      (node (ref "C18") (pin "1") (pinfunction "1_1") (pintype "passive"))
      (node (ref "C19") (pin "1") (pinfunction "1_1") (pintype "passive"))
      (node (ref "C20") (pin "1") (pinfunction "1_1") (pintype "passive"))
      (node (ref "C21") (pin "1") (pinfunction "1_1") (pintype "passive"))
      (node (ref "C22") (pin "1") (pinfunction "1_1") (pintype "passive"))
      (node (ref "C23") (pin "1") (pinfunction "1_1") (pintype "passive"))
      (node (ref "C24") (pin "1") (pinfunction "1_1") (pintype "passive"))
      (node (ref "C25") (pin "1") (pinfunction "1_1") (pintype "passive"))
      (node (ref "C26") (pin "1") (pinfunction "1_1") (pintype "passive"))
      (node (ref "C27") (pin "1") (pinfunction "1_1") (pintype "passive"))
      (node (ref "C28") (pin "1") (pinfunction "1_1") (pintype "passive"))
      (node (ref "C29") (pin "1") (pinfunction "1_1") (pintype "passive"))
      (node (ref "C30") (pin "1") (pinfunction "1_1") (pintype "passive"))
      (node (ref "C31") (pin "1") (pinfunction "1_1") (pintype "passive"))
      (node (ref "R3") (pin "2") (pinfunction "2_2") (pintype "passive"))
      (node (ref "U1") (pin "11") (pinfunction "AGND_11") (pintype "power_in"))
      (node (ref "U2") (pin "11") (pinfunction "AGND_11") (pintype "power_in"))
    )
    (net (code "129") (name "DGND") (class "Default")
      (node (ref "C1") (pin "1") (pinfunction "1_1") (pintype "passive"))
      (node (ref "C10") (pin "1") (pinfunction "1_1") (pintype "passive"))
      (node (ref "C11") (pin "2") (pinfunction "2_2") (pintype "passive"))
      (node (ref "C12") (pin "1") (pinfunction "1_1") (pintype "passive"))
      (node (ref "C13") (pin "2") (pinfunction "2_2") (pintype "passive"))
      (node (ref "C4") (pin "1") (pinfunction "1_1") (pintype "passive"))
      (node (ref "C5") (pin "1") (pinfunction "1_1") (pintype "passive"))
      (node (ref "C6") (pin "1") (pinfunction "1_1") (pintype "passive"))
      (node (ref "C7") (pin "1") (pinfunction "1_1") (pintype "passive"))
      (node (ref "C8") (pin "1") (pinfunction "1_1") (pintype "passive"))
      (node (ref "JP2") (pin "2") (pinfunction "C2_2") (pintype "passive"))
      (node (ref "R3") (pin "1") (pinfunction "1_1") (pintype "passive"))
      (node (ref "R7") (pin "1") (pinfunction "1_1") (pintype "passive"))
      (node (ref "R8") (pin "1") (pinfunction "1_1") (pintype "passive"))
      (node (ref "U1") (pin "1") (pinfunction "PGND_1") (pintype "power_in"))
      (node (ref "U1") (pin "2") (pinfunction "PGND_2") (pintype "power_in"))
      (node (ref "U2") (pin "1") (pinfunction "PGND_1") (pintype "power_in"))
      (node (ref "U2") (pin "2") (pinfunction "PGND_2") (pintype "power_in"))
      (node (ref "U3") (pin "1") (pinfunction "−VIN_1") (pintype "passive"))
      (node (ref "U4") (pin "2") (pinfunction "GND_2") (pintype "power_in"))
      (node (ref "U5") (pin "2") (pinfunction "GND_2") (pintype "power_in"))
      (node (ref "U5") (pin "4") (pinfunction "WDI_4") (pintype "power_in"))
      (node (ref "U8") (pin "16") (pinfunction "VSS_16") (pintype "power_in"))
      (node (ref "X15") (pin "10") (pinfunction "GND_10") (pintype "passive"))
      (node (ref "X15") (pin "12") (pinfunction "GND_12") (pintype "passive"))
      (node (ref "X15") (pin "4") (pinfunction "TDIS_4") (pintype "passive"))
      (node (ref "X15") (pin "8") (pinfunction "GND_8") (pintype "passive"))
      (node (ref "XTAL1") (pin "2") (pinfunction "GND_2") (pintype "passive"))
      (node (ref "XTAL1") (pin "4") (pinfunction "GND_4") (pintype "passive"))
    )
    (net (code "130") (name "GND_12V") (class "Default")
      (node (ref "C10") (pin "2") (pinfunction "2_2") (pintype "passive"))
      (node (ref "C9") (pin "1") (pinfunction "1_1") (pintype "passive"))
      (node (ref "U3") (pin "3") (pinfunction "−VOUT_3") (pintype "output"))
    )
    (net (code "131") (name "Net-(JP1-C2)") (class "Default")
      (node (ref "JP1") (pin "2") (pinfunction "C2_2") (pintype "passive"))
      (node (ref "R9") (pin "2") (pinfunction "2_2") (pintype "passive"))
    )
    (net (code "132") (name "Net-(JP2-C1)") (class "Default")
      (node (ref "JP2") (pin "1") (pinfunction "C1_1") (pintype "passive"))
      (node (ref "U5") (pin "3") (pinfunction "MRn_3") (pintype "power_in"))
    )
    (net (code "133") (name "Net-(U3-+VIN)") (class "Default")
      (node (ref "C8") (pin "2") (pinfunction "2_2") (pintype "passive"))
      (node (ref "L2") (pin "2") (pinfunction "2_2") (pintype "passive"))
      (node (ref "U3") (pin "2") (pinfunction "+VIN_2") (pintype "power_in"))
    )
    (net (code "134") (name "Net-(U4-RS)") (class "Default")
      (node (ref "R8") (pin "2") (pinfunction "2_2") (pintype "passive"))
      (node (ref "U4") (pin "8") (pinfunction "RS_8") (pintype "power_in"))
    )
    (net (code "135") (name "Net-(X15-EMU0)") (class "Default")
      (node (ref "R5") (pin "1") (pinfunction "1_1") (pintype "passive"))
      (node (ref "X15") (pin "13") (pinfunction "EMU0_13") (pintype "passive"))
    )
    (net (code "136") (name "Net-(X15-EMU1)") (class "Default")
      (node (ref "R6") (pin "1") (pinfunction "1_1") (pintype "passive"))
      (node (ref "X15") (pin "14") (pinfunction "EMU1_14") (pintype "passive"))
    )
    (net (code "137") (name "Net-(X15-PD)") (class "Default")
      (node (ref "R4") (pin "1") (pinfunction "1_1") (pintype "passive"))
      (node (ref "X15") (pin "5") (pinfunction "PD_5") (pintype "passive"))
    )
    (net (code "138") (name "unconnected-(U1-NC-Pad3)") (class "Default")
      (node (ref "U1") (pin "3") (pinfunction "NC_3") (pintype "power_in+no_connect"))
    )
    (net (code "139") (name "unconnected-(U1-NC-Pad4)") (class "Default")
      (node (ref "U1") (pin "4") (pinfunction "NC_4") (pintype "power_in+no_connect"))
    )
    (net (code "140") (name "unconnected-(U1-NC-Pad10)") (class "Default")
      (node (ref "U1") (pin "10") (pinfunction "NC_10") (pintype "power_in+no_connect"))
    )
    (net (code "141") (name "unconnected-(U1-PG-Pad8)") (class "Default")
      (node (ref "U1") (pin "8") (pinfunction "PG_8") (pintype "power_in+no_connect"))
    )
    (net (code "142") (name "unconnected-(U2-NC-Pad3)") (class "Default")
      (node (ref "U2") (pin "3") (pinfunction "NC_3") (pintype "power_in+no_connect"))
    )
    (net (code "143") (name "unconnected-(U2-NC-Pad4)") (class "Default")
      (node (ref "U2") (pin "4") (pinfunction "NC_4") (pintype "power_in+no_connect"))
    )
    (net (code "144") (name "unconnected-(U2-NC-Pad10)") (class "Default")
      (node (ref "U2") (pin "10") (pinfunction "NC_10") (pintype "power_in+no_connect"))
    )
    (net (code "145") (name "unconnected-(U2-PG-Pad8)") (class "Default")
      (node (ref "U2") (pin "8") (pinfunction "PG_8") (pintype "power_in+no_connect"))
    )
    (net (code "146") (name "unconnected-(X15-KEY-Pad6)") (class "Default")
      (node (ref "X15") (pin "6") (pinfunction "KEY_6") (pintype "passive+no_connect"))
    )
  )
)
